# Control_Board_v1_0.net
KiCad netlist of a schematic drawn in EAGLE
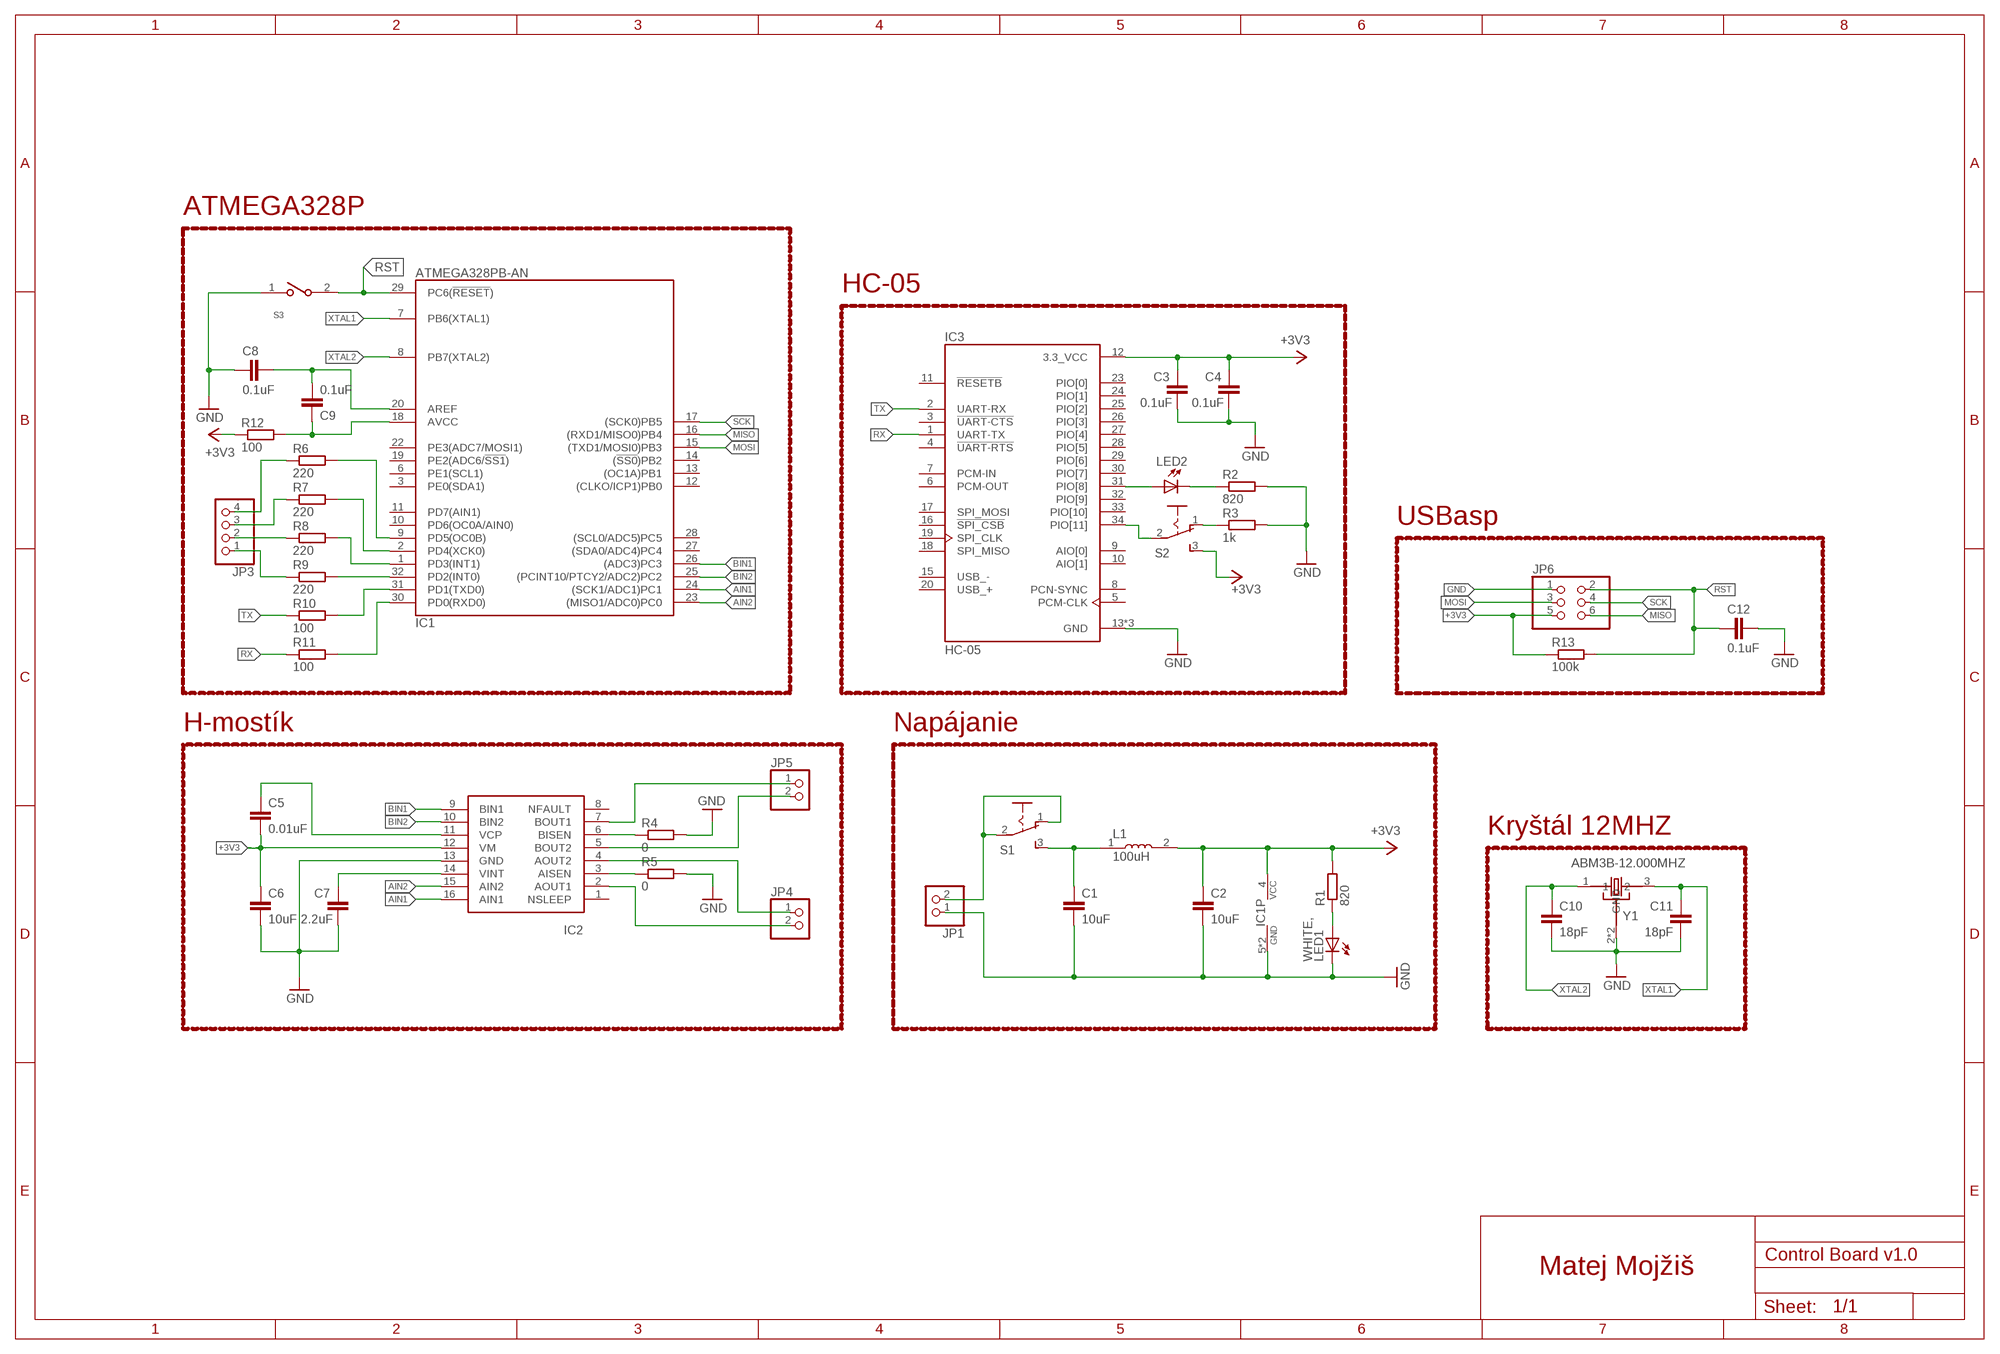
[diagram p0: schematic, sheet 1]

(export (version "E")
  (design (tool "Eeschema 10.0.6"))
  (components
    (comp (ref "C1")
      (value "10uF")
      (footprint "eagle-import:C0805")
      (libsource (lib "eagle-import") (part "C-EUC0805"))
    )
    (comp (ref "C2")
      (value "10uF")
      (footprint "eagle-import:C0805")
      (libsource (lib "eagle-import") (part "C-EUC0805"))
    )
    (comp (ref "C3")
      (value "0.1uF")
      (footprint "eagle-import:C0805")
      (libsource (lib "eagle-import") (part "C-EUC0805"))
    )
    (comp (ref "C4")
      (value "0.1uF")
      (footprint "eagle-import:C0805")
      (libsource (lib "eagle-import") (part "C-EUC0805"))
    )
    (comp (ref "C5")
      (value "0.01uF")
      (footprint "eagle-import:C0805")
      (libsource (lib "eagle-import") (part "C-EUC0805"))
    )
    (comp (ref "C6")
      (value "10uF")
      (footprint "eagle-import:C0805")
      (libsource (lib "eagle-import") (part "C-EUC0805"))
    )
    (comp (ref "C7")
      (value "2.2uF")
      (footprint "eagle-import:C0805")
      (libsource (lib "eagle-import") (part "C-EUC0805"))
    )
    (comp (ref "C8")
      (value "0.1uF")
      (footprint "eagle-import:C0805")
      (libsource (lib "eagle-import") (part "C-EUC0805"))
    )
    (comp (ref "C9")
      (value "0.1uF")
      (footprint "eagle-import:C0805")
      (libsource (lib "eagle-import") (part "C-EUC0805"))
    )
    (comp (ref "C10")
      (value "18pF")
      (footprint "eagle-import:C0805")
      (libsource (lib "eagle-import") (part "C-EUC0805"))
    )
    (comp (ref "C11")
      (value "18pF")
      (footprint "eagle-import:C0805")
      (libsource (lib "eagle-import") (part "C-EUC0805"))
    )
    (comp (ref "C12")
      (value "0.1uF")
      (footprint "eagle-import:C0805")
      (libsource (lib "eagle-import") (part "C-EUC0805"))
    )
    (comp (ref "IC1")
      (value "ATMEGA328PB-AN")
      (footprint "eagle-import:QFP32_7X7_0.80")
      (libsource (lib "eagle-import") (part "ATMEGA328PB-AN"))
    )
    (comp (ref "IC2")
      (value "DVR8833SUPERFICIAL")
      (footprint "eagle-import:PWP16")
      (libsource (lib "eagle-import") (part "DVR8833SUPERFICIAL"))
    )
    (comp (ref "IC3")
      (value "HC-05")
      (footprint "eagle-import:XCVR_HC-05")
      (fields (field (name "MF") "Bel Power solution"))
      (libsource (lib "eagle-import") (part "HC-05"))
    )
    (comp (ref "JP1")
      (value "PINHD-1X2/90")
      (footprint "eagle-import:1X02_90")
      (libsource (lib "eagle-import") (part "PINHD-1X2/90"))
    )
    (comp (ref "JP3")
      (value "PINHD-1X4")
      (footprint "eagle-import:1X04")
      (libsource (lib "eagle-import") (part "PINHD-1X4"))
    )
    (comp (ref "JP4")
      (value "PINHD-1X2/90")
      (footprint "eagle-import:1X02_90")
      (libsource (lib "eagle-import") (part "PINHD-1X2/90"))
    )
    (comp (ref "JP5")
      (value "PINHD-1X2/90")
      (footprint "eagle-import:1X02_90")
      (libsource (lib "eagle-import") (part "PINHD-1X2/90"))
    )
    (comp (ref "JP6")
      (value "PINHD-2X3")
      (footprint "eagle-import:2X03")
      (libsource (lib "eagle-import") (part "PINHD-2X3"))
    )
    (comp (ref "L1")
      (value "100uH")
      (footprint "eagle-import:INDC2012X87N")
      (fields (field (name "MF") "TDK") (field (name "MP") "MLF2012C330KT000"))
      (libsource (lib "eagle-import") (part "MLF2012C330KT000"))
    )
    (comp (ref "LED1")
      (value "WHITE,")
      (footprint "eagle-import:CHIPLED_0805")
      (libsource (lib "eagle-import") (part "LEDCHIPLED_0805"))
    )
    (comp (ref "LED2")
      (value "RED")
      (footprint "eagle-import:CHIPLED_0805")
      (libsource (lib "eagle-import") (part "LEDCHIPLED_0805"))
    )
    (comp (ref "R1")
      (value "820")
      (footprint "eagle-import:R0805")
      (libsource (lib "eagle-import") (part "R-EU_R0805"))
    )
    (comp (ref "R2")
      (value "820")
      (footprint "eagle-import:R0805")
      (libsource (lib "eagle-import") (part "R-EU_R0805"))
    )
    (comp (ref "R3")
      (value "1k")
      (footprint "eagle-import:R0805")
      (libsource (lib "eagle-import") (part "R-EU_R0805"))
    )
    (comp (ref "R4")
      (value "0")
      (footprint "eagle-import:R0805")
      (libsource (lib "eagle-import") (part "R-EU_R0805"))
    )
    (comp (ref "R5")
      (value "0")
      (footprint "eagle-import:R0805")
      (libsource (lib "eagle-import") (part "R-EU_R0805"))
    )
    (comp (ref "R6")
      (value "220")
      (footprint "eagle-import:R0805")
      (libsource (lib "eagle-import") (part "R-EU_R0805"))
    )
    (comp (ref "R7")
      (value "220")
      (footprint "eagle-import:R0805")
      (libsource (lib "eagle-import") (part "R-EU_R0805"))
    )
    (comp (ref "R8")
      (value "220")
      (footprint "eagle-import:R0805")
      (libsource (lib "eagle-import") (part "R-EU_R0805"))
    )
    (comp (ref "R9")
      (value "220")
      (footprint "eagle-import:R0805")
      (libsource (lib "eagle-import") (part "R-EU_R0805"))
    )
    (comp (ref "R10")
      (value "100")
      (footprint "eagle-import:R0805")
      (libsource (lib "eagle-import") (part "R-EU_R0805"))
    )
    (comp (ref "R11")
      (value "100")
      (footprint "eagle-import:R0805")
      (libsource (lib "eagle-import") (part "R-EU_R0805"))
    )
    (comp (ref "R12")
      (value "100")
      (footprint "eagle-import:R0805")
      (libsource (lib "eagle-import") (part "R-EU_R0805"))
    )
    (comp (ref "R13")
      (value "100k")
      (footprint "eagle-import:R0805")
      (libsource (lib "eagle-import") (part "R-EU_R0805"))
    )
    (comp (ref "S1")
      (value "255SB")
      (footprint "eagle-import:255SB")
      (libsource (lib "eagle-import") (part "255SB"))
    )
    (comp (ref "S2")
      (value "255SB")
      (footprint "eagle-import:255SB")
      (libsource (lib "eagle-import") (part "255SB"))
    )
    (comp (ref "S3")
      (value "147873-2")
      (footprint "eagle-import:SW_147873-2")
      (fields (field (name "MF") "TE Connectivity"))
      (libsource (lib "eagle-import") (part "147873-2"))
    )
    (comp (ref "Y1")
      (value "ABM3B-12.000MHZ")
      (footprint "eagle-import:OSCSC500X320X110-4N")
      (fields (field (name "MF") "Abracon") (field (name "MP") "ABM3B-8.000MHZ-B2-T"))
      (libsource (lib "eagle-import") (part "ABM3B-8.000MHZ-B2-T"))
    )
  )
  (nets
    (net (code "1") (name "+3V3") (class "Default")
      (node (ref "C2") (pin "1") (pinfunction "1_1") (pintype "passive"))
      (node (ref "C3") (pin "1") (pinfunction "1_1") (pintype "passive"))
      (node (ref "C4") (pin "1") (pinfunction "1_1") (pintype "passive"))
      (node (ref "C5") (pin "2") (pinfunction "2_2") (pintype "passive"))
      (node (ref "C6") (pin "1") (pinfunction "1_1") (pintype "passive"))
      (node (ref "IC1") (pin "4") (pinfunction "VCC_4") (pintype "power_in"))
      (node (ref "IC2") (pin "12") (pinfunction "VM_12") (pintype "bidirectional"))
      (node (ref "IC3") (pin "12") (pinfunction "3.3_VCC_12") (pintype "power_in"))
      (node (ref "JP6") (pin "5") (pinfunction "5_5") (pintype "passive"))
      (node (ref "L1") (pin "2") (pinfunction "2_2") (pintype "passive"))
      (node (ref "R1") (pin "2") (pinfunction "2_2") (pintype "passive"))
      (node (ref "R12") (pin "1") (pinfunction "1_1") (pintype "passive"))
      (node (ref "R13") (pin "1") (pinfunction "1_1") (pintype "passive"))
      (node (ref "S2") (pin "3") (pinfunction "S_3") (pintype "passive"))
    )
    (net (code "2") (name "AIN1") (class "Default")
      (node (ref "IC1") (pin "24") (pinfunction "(SCK1/ADC1)PC1_24") (pintype "bidirectional"))
      (node (ref "IC2") (pin "16") (pinfunction "AIN1_16") (pintype "bidirectional"))
    )
    (net (code "3") (name "AIN2") (class "Default")
      (node (ref "IC1") (pin "23") (pinfunction "(MISO1/ADC0)PC0_23") (pintype "bidirectional"))
      (node (ref "IC2") (pin "15") (pinfunction "AIN2_15") (pintype "bidirectional"))
    )
    (net (code "4") (name "BIN1") (class "Default")
      (node (ref "IC1") (pin "26") (pinfunction "(ADC3)PC3_26") (pintype "bidirectional"))
      (node (ref "IC2") (pin "9") (pinfunction "BIN1_9") (pintype "bidirectional"))
    )
    (net (code "5") (name "BIN2") (class "Default")
      (node (ref "IC1") (pin "25") (pinfunction "(PCINT10/PTCY2/ADC2)PC2_25") (pintype "bidirectional"))
      (node (ref "IC2") (pin "10") (pinfunction "BIN2_10") (pintype "bidirectional"))
    )
    (net (code "6") (name "GND") (class "Default")
      (node (ref "C1") (pin "2") (pinfunction "2_2") (pintype "passive"))
      (node (ref "C10") (pin "2") (pinfunction "2_2") (pintype "passive"))
      (node (ref "C11") (pin "2") (pinfunction "2_2") (pintype "passive"))
      (node (ref "C12") (pin "1") (pinfunction "1_1") (pintype "passive"))
      (node (ref "C2") (pin "2") (pinfunction "2_2") (pintype "passive"))
      (node (ref "C3") (pin "2") (pinfunction "2_2") (pintype "passive"))
      (node (ref "C4") (pin "2") (pinfunction "2_2") (pintype "passive"))
      (node (ref "C6") (pin "2") (pinfunction "2_2") (pintype "passive"))
      (node (ref "C7") (pin "2") (pinfunction "2_2") (pintype "passive"))
      (node (ref "C8") (pin "2") (pinfunction "2_2") (pintype "passive"))
      (node (ref "IC1") (pin "21") (pinfunction "GND_21") (pintype "power_in"))
      (node (ref "IC1") (pin "5") (pinfunction "GND_5") (pintype "power_in"))
      (node (ref "IC2") (pin "13") (pinfunction "GND_13") (pintype "bidirectional"))
      (node (ref "IC3") (pin "13") (pinfunction "GND_13") (pintype "power_in"))
      (node (ref "IC3") (pin "21") (pinfunction "GND_21") (pintype "power_in"))
      (node (ref "IC3") (pin "22") (pinfunction "GND_22") (pintype "power_in"))
      (node (ref "JP1") (pin "1") (pinfunction "1_1") (pintype "passive"))
      (node (ref "JP6") (pin "1") (pinfunction "1_1") (pintype "passive"))
      (node (ref "LED1") (pin "C") (pinfunction "C_C") (pintype "passive"))
      (node (ref "R2") (pin "2") (pinfunction "2_2") (pintype "passive"))
      (node (ref "R3") (pin "2") (pinfunction "2_2") (pintype "passive"))
      (node (ref "R4") (pin "2") (pinfunction "2_2") (pintype "passive"))
      (node (ref "R5") (pin "2") (pinfunction "2_2") (pintype "passive"))
      (node (ref "S3") (pin "1") (pinfunction "1_1") (pintype "passive"))
      (node (ref "Y1") (pin "2") (pinfunction "GND_2") (pintype "passive"))
      (node (ref "Y1") (pin "4") (pinfunction "GND_4") (pintype "passive"))
    )
    (net (code "7") (name "MISO") (class "Default")
      (node (ref "IC1") (pin "16") (pinfunction "(RXD1/MISO0)PB4_16") (pintype "bidirectional"))
      (node (ref "JP6") (pin "6") (pinfunction "6_6") (pintype "passive"))
    )
    (net (code "8") (name "MOSI") (class "Default")
      (node (ref "IC1") (pin "15") (pinfunction "(TXD1/MOSI0)PB3_15") (pintype "bidirectional"))
      (node (ref "JP6") (pin "3") (pinfunction "3_3") (pintype "passive"))
    )
    (net (code "9") (name "Net-(IC1A-AREF)") (class "Default")
      (node (ref "C8") (pin "1") (pinfunction "1_1") (pintype "passive"))
      (node (ref "C9") (pin "2") (pinfunction "2_2") (pintype "passive"))
      (node (ref "IC1") (pin "20") (pinfunction "AREF_20") (pintype "passive"))
    )
    (net (code "10") (name "Net-(IC1A-AVCC)") (class "Default")
      (node (ref "C9") (pin "1") (pinfunction "1_1") (pintype "passive"))
      (node (ref "IC1") (pin "18") (pinfunction "AVCC_18") (pintype "power_in"))
      (node (ref "R12") (pin "2") (pinfunction "2_2") (pintype "passive"))
    )
    (net (code "11") (name "Net-(IC1A-PD0(RXD0))") (class "Default")
      (node (ref "IC1") (pin "30") (pinfunction "PD0(RXD0)_30") (pintype "bidirectional"))
      (node (ref "R11") (pin "2") (pinfunction "2_2") (pintype "passive"))
    )
    (net (code "12") (name "Net-(IC1A-PD1(TXD0))") (class "Default")
      (node (ref "IC1") (pin "31") (pinfunction "PD1(TXD0)_31") (pintype "bidirectional"))
      (node (ref "R10") (pin "2") (pinfunction "2_2") (pintype "passive"))
    )
    (net (code "13") (name "Net-(IC1A-PD2(INT0))") (class "Default")
      (node (ref "IC1") (pin "32") (pinfunction "PD2(INT0)_32") (pintype "bidirectional"))
      (node (ref "R9") (pin "2") (pinfunction "2_2") (pintype "passive"))
    )
    (net (code "14") (name "Net-(IC1A-PD3(INT1))") (class "Default")
      (node (ref "IC1") (pin "1") (pinfunction "PD3(INT1)_1") (pintype "bidirectional"))
      (node (ref "R8") (pin "2") (pinfunction "2_2") (pintype "passive"))
    )
    (net (code "15") (name "Net-(IC1A-PD4(XCK0))") (class "Default")
      (node (ref "IC1") (pin "2") (pinfunction "PD4(XCK0)_2") (pintype "bidirectional"))
      (node (ref "R7") (pin "2") (pinfunction "2_2") (pintype "passive"))
    )
    (net (code "16") (name "Net-(IC1A-PD5(OC0B))") (class "Default")
      (node (ref "IC1") (pin "9") (pinfunction "PD5(OC0B)_9") (pintype "bidirectional"))
      (node (ref "R6") (pin "2") (pinfunction "2_2") (pintype "passive"))
    )
    (net (code "17") (name "Net-(IC2-AISEN)") (class "Default")
      (node (ref "IC2") (pin "3") (pinfunction "AISEN_3") (pintype "bidirectional"))
      (node (ref "R5") (pin "1") (pinfunction "1_1") (pintype "passive"))
    )
    (net (code "18") (name "Net-(IC2-AOUT1)") (class "Default")
      (node (ref "IC2") (pin "2") (pinfunction "AOUT1_2") (pintype "bidirectional"))
      (node (ref "JP4") (pin "2") (pinfunction "2_2") (pintype "passive"))
    )
    (net (code "19") (name "Net-(IC2-AOUT2)") (class "Default")
      (node (ref "IC2") (pin "4") (pinfunction "AOUT2_4") (pintype "bidirectional"))
      (node (ref "JP4") (pin "1") (pinfunction "1_1") (pintype "passive"))
    )
    (net (code "20") (name "Net-(IC2-BISEN)") (class "Default")
      (node (ref "IC2") (pin "6") (pinfunction "BISEN_6") (pintype "bidirectional"))
      (node (ref "R4") (pin "1") (pinfunction "1_1") (pintype "passive"))
    )
    (net (code "21") (name "Net-(IC2-BOUT1)") (class "Default")
      (node (ref "IC2") (pin "7") (pinfunction "BOUT1_7") (pintype "bidirectional"))
      (node (ref "JP5") (pin "1") (pinfunction "1_1") (pintype "passive"))
    )
    (net (code "22") (name "Net-(IC2-BOUT2)") (class "Default")
      (node (ref "IC2") (pin "5") (pinfunction "BOUT2_5") (pintype "bidirectional"))
      (node (ref "JP5") (pin "2") (pinfunction "2_2") (pintype "passive"))
    )
    (net (code "23") (name "Net-(IC2-VCP)") (class "Default")
      (node (ref "C5") (pin "1") (pinfunction "1_1") (pintype "passive"))
      (node (ref "IC2") (pin "11") (pinfunction "VCP_11") (pintype "bidirectional"))
    )
    (net (code "24") (name "Net-(IC2-VINT)") (class "Default")
      (node (ref "C7") (pin "1") (pinfunction "1_1") (pintype "passive"))
      (node (ref "IC2") (pin "14") (pinfunction "VINT_14") (pintype "bidirectional"))
    )
    (net (code "25") (name "Net-(IC3-PIO[8])") (class "Default")
      (node (ref "IC3") (pin "31") (pinfunction "PIO[8]_31") (pintype "bidirectional"))
      (node (ref "LED2") (pin "A") (pinfunction "A_A") (pintype "passive"))
    )
    (net (code "26") (name "Net-(IC3-PIO[11])") (class "Default")
      (node (ref "IC3") (pin "34") (pinfunction "PIO[11]_34") (pintype "bidirectional"))
      (node (ref "S2") (pin "2") (pinfunction "P_2") (pintype "passive"))
    )
    (net (code "27") (name "Net-(JP3-Pad1)") (class "Default")
      (node (ref "JP3") (pin "1") (pinfunction "1_1") (pintype "passive"))
      (node (ref "R9") (pin "1") (pinfunction "1_1") (pintype "passive"))
    )
    (net (code "28") (name "Net-(JP3-Pad2)") (class "Default")
      (node (ref "JP3") (pin "2") (pinfunction "2_2") (pintype "passive"))
      (node (ref "R8") (pin "1") (pinfunction "1_1") (pintype "passive"))
    )
    (net (code "29") (name "Net-(JP3-Pad3)") (class "Default")
      (node (ref "JP3") (pin "3") (pinfunction "3_3") (pintype "passive"))
      (node (ref "R7") (pin "1") (pinfunction "1_1") (pintype "passive"))
    )
    (net (code "30") (name "Net-(JP3-Pad4)") (class "Default")
      (node (ref "JP3") (pin "4") (pinfunction "4_4") (pintype "passive"))
      (node (ref "R6") (pin "1") (pinfunction "1_1") (pintype "passive"))
    )
    (net (code "31") (name "Net-(LED1-PadA)") (class "Default")
      (node (ref "LED1") (pin "A") (pinfunction "A_A") (pintype "passive"))
      (node (ref "R1") (pin "1") (pinfunction "1_1") (pintype "passive"))
    )
    (net (code "32") (name "Net-(LED2-PadC)") (class "Default")
      (node (ref "LED2") (pin "C") (pinfunction "C_C") (pintype "passive"))
      (node (ref "R2") (pin "1") (pinfunction "1_1") (pintype "passive"))
    )
    (net (code "33") (name "Net-(S1-O)") (class "Default")
      (node (ref "JP1") (pin "2") (pinfunction "2_2") (pintype "passive"))
      (node (ref "S1") (pin "1") (pinfunction "O_1") (pintype "passive"))
      (node (ref "S1") (pin "2") (pinfunction "P_2") (pintype "passive"))
    )
    (net (code "34") (name "Net-(S1-S)") (class "Default")
      (node (ref "C1") (pin "1") (pinfunction "1_1") (pintype "passive"))
      (node (ref "L1") (pin "1") (pinfunction "1_1") (pintype "passive"))
      (node (ref "S1") (pin "3") (pinfunction "S_3") (pintype "passive"))
    )
    (net (code "35") (name "Net-(S2-O)") (class "Default")
      (node (ref "R3") (pin "1") (pinfunction "1_1") (pintype "passive"))
      (node (ref "S2") (pin "1") (pinfunction "O_1") (pintype "passive"))
    )
    (net (code "36") (name "RST") (class "Default")
      (node (ref "C12") (pin "2") (pinfunction "2_2") (pintype "passive"))
      (node (ref "IC1") (pin "29") (pinfunction "PC6(~{RESET})_29") (pintype "bidirectional"))
      (node (ref "JP6") (pin "2") (pinfunction "2_2") (pintype "passive"))
      (node (ref "R13") (pin "2") (pinfunction "2_2") (pintype "passive"))
      (node (ref "S3") (pin "2") (pinfunction "2_2") (pintype "passive"))
    )
    (net (code "37") (name "RX") (class "Default")
      (node (ref "IC3") (pin "1") (pinfunction "UART-TX_1") (pintype "output"))
      (node (ref "R11") (pin "1") (pinfunction "1_1") (pintype "passive"))
    )
    (net (code "38") (name "SCK") (class "Default")
      (node (ref "IC1") (pin "17") (pinfunction "(SCK0)PB5_17") (pintype "bidirectional"))
      (node (ref "JP6") (pin "4") (pinfunction "4_4") (pintype "passive"))
    )
    (net (code "39") (name "TX") (class "Default")
      (node (ref "IC3") (pin "2") (pinfunction "UART-RX_2") (pintype "input"))
      (node (ref "R10") (pin "1") (pinfunction "1_1") (pintype "passive"))
    )
    (net (code "40") (name "XTAL1") (class "Default")
      (node (ref "C11") (pin "1") (pinfunction "1_1") (pintype "passive"))
      (node (ref "IC1") (pin "7") (pinfunction "PB6(XTAL1)_7") (pintype "bidirectional"))
      (node (ref "Y1") (pin "3") (pinfunction "2_3") (pintype "passive"))
    )
    (net (code "41") (name "XTAL2") (class "Default")
      (node (ref "C10") (pin "1") (pinfunction "1_1") (pintype "passive"))
      (node (ref "IC1") (pin "8") (pinfunction "PB7(XTAL2)_8") (pintype "bidirectional"))
      (node (ref "Y1") (pin "1") (pinfunction "1_1") (pintype "passive"))
    )
    (net (code "42") (name "unconnected-(IC1A-(CLKO{slash}ICP1)PB0-Pad12)") (class "Default")
      (node (ref "IC1") (pin "12") (pinfunction "(CLKO/ICP1)PB0_12") (pintype "bidirectional"))
    )
    (net (code "43") (name "unconnected-(IC1A-(OC1A)PB1-Pad13)") (class "Default")
      (node (ref "IC1") (pin "13") (pinfunction "(OC1A)PB1_13") (pintype "bidirectional"))
    )
    (net (code "44") (name "unconnected-(IC1A-(SCL0{slash}ADC5)PC5-Pad28)") (class "Default")
      (node (ref "IC1") (pin "28") (pinfunction "(SCL0/ADC5)PC5_28") (pintype "bidirectional"))
    )
    (net (code "45") (name "unconnected-(IC1A-(SDA0{slash}ADC4)PC4-Pad27)") (class "Default")
      (node (ref "IC1") (pin "27") (pinfunction "(SDA0/ADC4)PC4_27") (pintype "bidirectional"))
    )
    (net (code "46") (name "unconnected-(IC1A-(~{SS0})PB2-Pad14)") (class "Default")
      (node (ref "IC1") (pin "14") (pinfunction "(~{SS0})PB2_14") (pintype "bidirectional"))
    )
    (net (code "47") (name "unconnected-(IC1A-PD6(OC0A{slash}AIN0)-Pad10)") (class "Default")
      (node (ref "IC1") (pin "10") (pinfunction "PD6(OC0A/AIN0)_10") (pintype "bidirectional"))
    )
    (net (code "48") (name "unconnected-(IC1A-PD7(AIN1)-Pad11)") (class "Default")
      (node (ref "IC1") (pin "11") (pinfunction "PD7(AIN1)_11") (pintype "bidirectional"))
    )
    (net (code "49") (name "unconnected-(IC1A-PE0(SDA1)-Pad3)") (class "Default")
      (node (ref "IC1") (pin "3") (pinfunction "PE0(SDA1)_3") (pintype "bidirectional"))
    )
    (net (code "50") (name "unconnected-(IC1A-PE1(SCL1)-Pad6)") (class "Default")
      (node (ref "IC1") (pin "6") (pinfunction "PE1(SCL1)_6") (pintype "bidirectional"))
    )
    (net (code "51") (name "unconnected-(IC1A-PE2(ADC6{slash}~{SS1})-Pad19)") (class "Default")
      (node (ref "IC1") (pin "19") (pinfunction "PE2(ADC6/~{SS1})_19") (pintype "bidirectional"))
    )
    (net (code "52") (name "unconnected-(IC1A-PE3(ADC7{slash}MOSI1)-Pad22)") (class "Default")
      (node (ref "IC1") (pin "22") (pinfunction "PE3(ADC7/MOSI1)_22") (pintype "bidirectional"))
    )
    (net (code "53") (name "unconnected-(IC2-NFAULT-Pad8)") (class "Default")
      (node (ref "IC2") (pin "8") (pinfunction "NFAULT_8") (pintype "bidirectional"))
    )
    (net (code "54") (name "unconnected-(IC2-NSLEEP-Pad1)") (class "Default")
      (node (ref "IC2") (pin "1") (pinfunction "NSLEEP_1") (pintype "bidirectional"))
    )
    (net (code "55") (name "unconnected-(IC3-AIO[0]-Pad9)") (class "Default")
      (node (ref "IC3") (pin "9") (pinfunction "AIO[0]_9") (pintype "bidirectional"))
    )
    (net (code "56") (name "unconnected-(IC3-AIO[1]-Pad10)") (class "Default")
      (node (ref "IC3") (pin "10") (pinfunction "AIO[1]_10") (pintype "bidirectional"))
    )
    (net (code "57") (name "unconnected-(IC3-PCM-CLK-Pad5)") (class "Default")
      (node (ref "IC3") (pin "5") (pinfunction "PCM-CLK_5") (pintype "bidirectional"))
    )
    (net (code "58") (name "unconnected-(IC3-PCM-IN-Pad7)") (class "Default")
      (node (ref "IC3") (pin "7") (pinfunction "PCM-IN_7") (pintype "input"))
    )
    (net (code "59") (name "unconnected-(IC3-PCM-OUT-Pad6)") (class "Default")
      (node (ref "IC3") (pin "6") (pinfunction "PCM-OUT_6") (pintype "output"))
    )
    (net (code "60") (name "unconnected-(IC3-PCN-SYNC-Pad8)") (class "Default")
      (node (ref "IC3") (pin "8") (pinfunction "PCN-SYNC_8") (pintype "bidirectional"))
    )
    (net (code "61") (name "unconnected-(IC3-PIO[0]-Pad23)") (class "Default")
      (node (ref "IC3") (pin "23") (pinfunction "PIO[0]_23") (pintype "bidirectional"))
    )
    (net (code "62") (name "unconnected-(IC3-PIO[1]-Pad24)") (class "Default")
      (node (ref "IC3") (pin "24") (pinfunction "PIO[1]_24") (pintype "bidirectional"))
    )
    (net (code "63") (name "unconnected-(IC3-PIO[2]-Pad25)") (class "Default")
      (node (ref "IC3") (pin "25") (pinfunction "PIO[2]_25") (pintype "bidirectional"))
    )
    (net (code "64") (name "unconnected-(IC3-PIO[3]-Pad26)") (class "Default")
      (node (ref "IC3") (pin "26") (pinfunction "PIO[3]_26") (pintype "bidirectional"))
    )
    (net (code "65") (name "unconnected-(IC3-PIO[4]-Pad27)") (class "Default")
      (node (ref "IC3") (pin "27") (pinfunction "PIO[4]_27") (pintype "bidirectional"))
    )
    (net (code "66") (name "unconnected-(IC3-PIO[5]-Pad28)") (class "Default")
      (node (ref "IC3") (pin "28") (pinfunction "PIO[5]_28") (pintype "bidirectional"))
    )
    (net (code "67") (name "unconnected-(IC3-PIO[6]-Pad29)") (class "Default")
      (node (ref "IC3") (pin "29") (pinfunction "PIO[6]_29") (pintype "bidirectional"))
    )
    (net (code "68") (name "unconnected-(IC3-PIO[7]-Pad30)") (class "Default")
      (node (ref "IC3") (pin "30") (pinfunction "PIO[7]_30") (pintype "bidirectional"))
    )
    (net (code "69") (name "unconnected-(IC3-PIO[9]-Pad32)") (class "Default")
      (node (ref "IC3") (pin "32") (pinfunction "PIO[9]_32") (pintype "bidirectional"))
    )
    (net (code "70") (name "unconnected-(IC3-PIO[10]-Pad33)") (class "Default")
      (node (ref "IC3") (pin "33") (pinfunction "PIO[10]_33") (pintype "bidirectional"))
    )
    (net (code "71") (name "unconnected-(IC3-SPI_CLK-Pad19)") (class "Default")
      (node (ref "IC3") (pin "19") (pinfunction "SPI_CLK_19") (pintype "input"))
    )
    (net (code "72") (name "unconnected-(IC3-SPI_MISO-Pad18)") (class "Default")
      (node (ref "IC3") (pin "18") (pinfunction "SPI_MISO_18") (pintype "output"))
    )
    (net (code "73") (name "unconnected-(IC3-SPI_MOSI-Pad17)") (class "Default")
      (node (ref "IC3") (pin "17") (pinfunction "SPI_MOSI_17") (pintype "input"))
    )
    (net (code "74") (name "unconnected-(IC3-USB_+-Pad20)") (class "Default")
      (node (ref "IC3") (pin "20") (pinfunction "USB_+_20") (pintype "bidirectional"))
    )
    (net (code "75") (name "unconnected-(IC3-USB_--Pad15)") (class "Default")
      (node (ref "IC3") (pin "15") (pinfunction "USB_-_15") (pintype "bidirectional"))
    )
    (net (code "76") (name "unconnected-(IC3-~{RESETB}-Pad11)") (class "Default")
      (node (ref "IC3") (pin "11") (pinfunction "~{RESETB}_11") (pintype "input"))
    )
    (net (code "77") (name "unconnected-(IC3-~{SPI_CSB}-Pad16)") (class "Default")
      (node (ref "IC3") (pin "16") (pinfunction "~{SPI_CSB}_16") (pintype "input"))
    )
    (net (code "78") (name "unconnected-(IC3-~{UART-CTS}-Pad3)") (class "Default")
      (node (ref "IC3") (pin "3") (pinfunction "~{UART-CTS}_3") (pintype "input"))
    )
    (net (code "79") (name "unconnected-(IC3-~{UART-RTS}-Pad4)") (class "Default")
      (node (ref "IC3") (pin "4") (pinfunction "~{UART-RTS}_4") (pintype "output"))
    )
  )
)
